# tobi_arduino_version.net
KiCad netlist of a schematic drawn in EAGLE
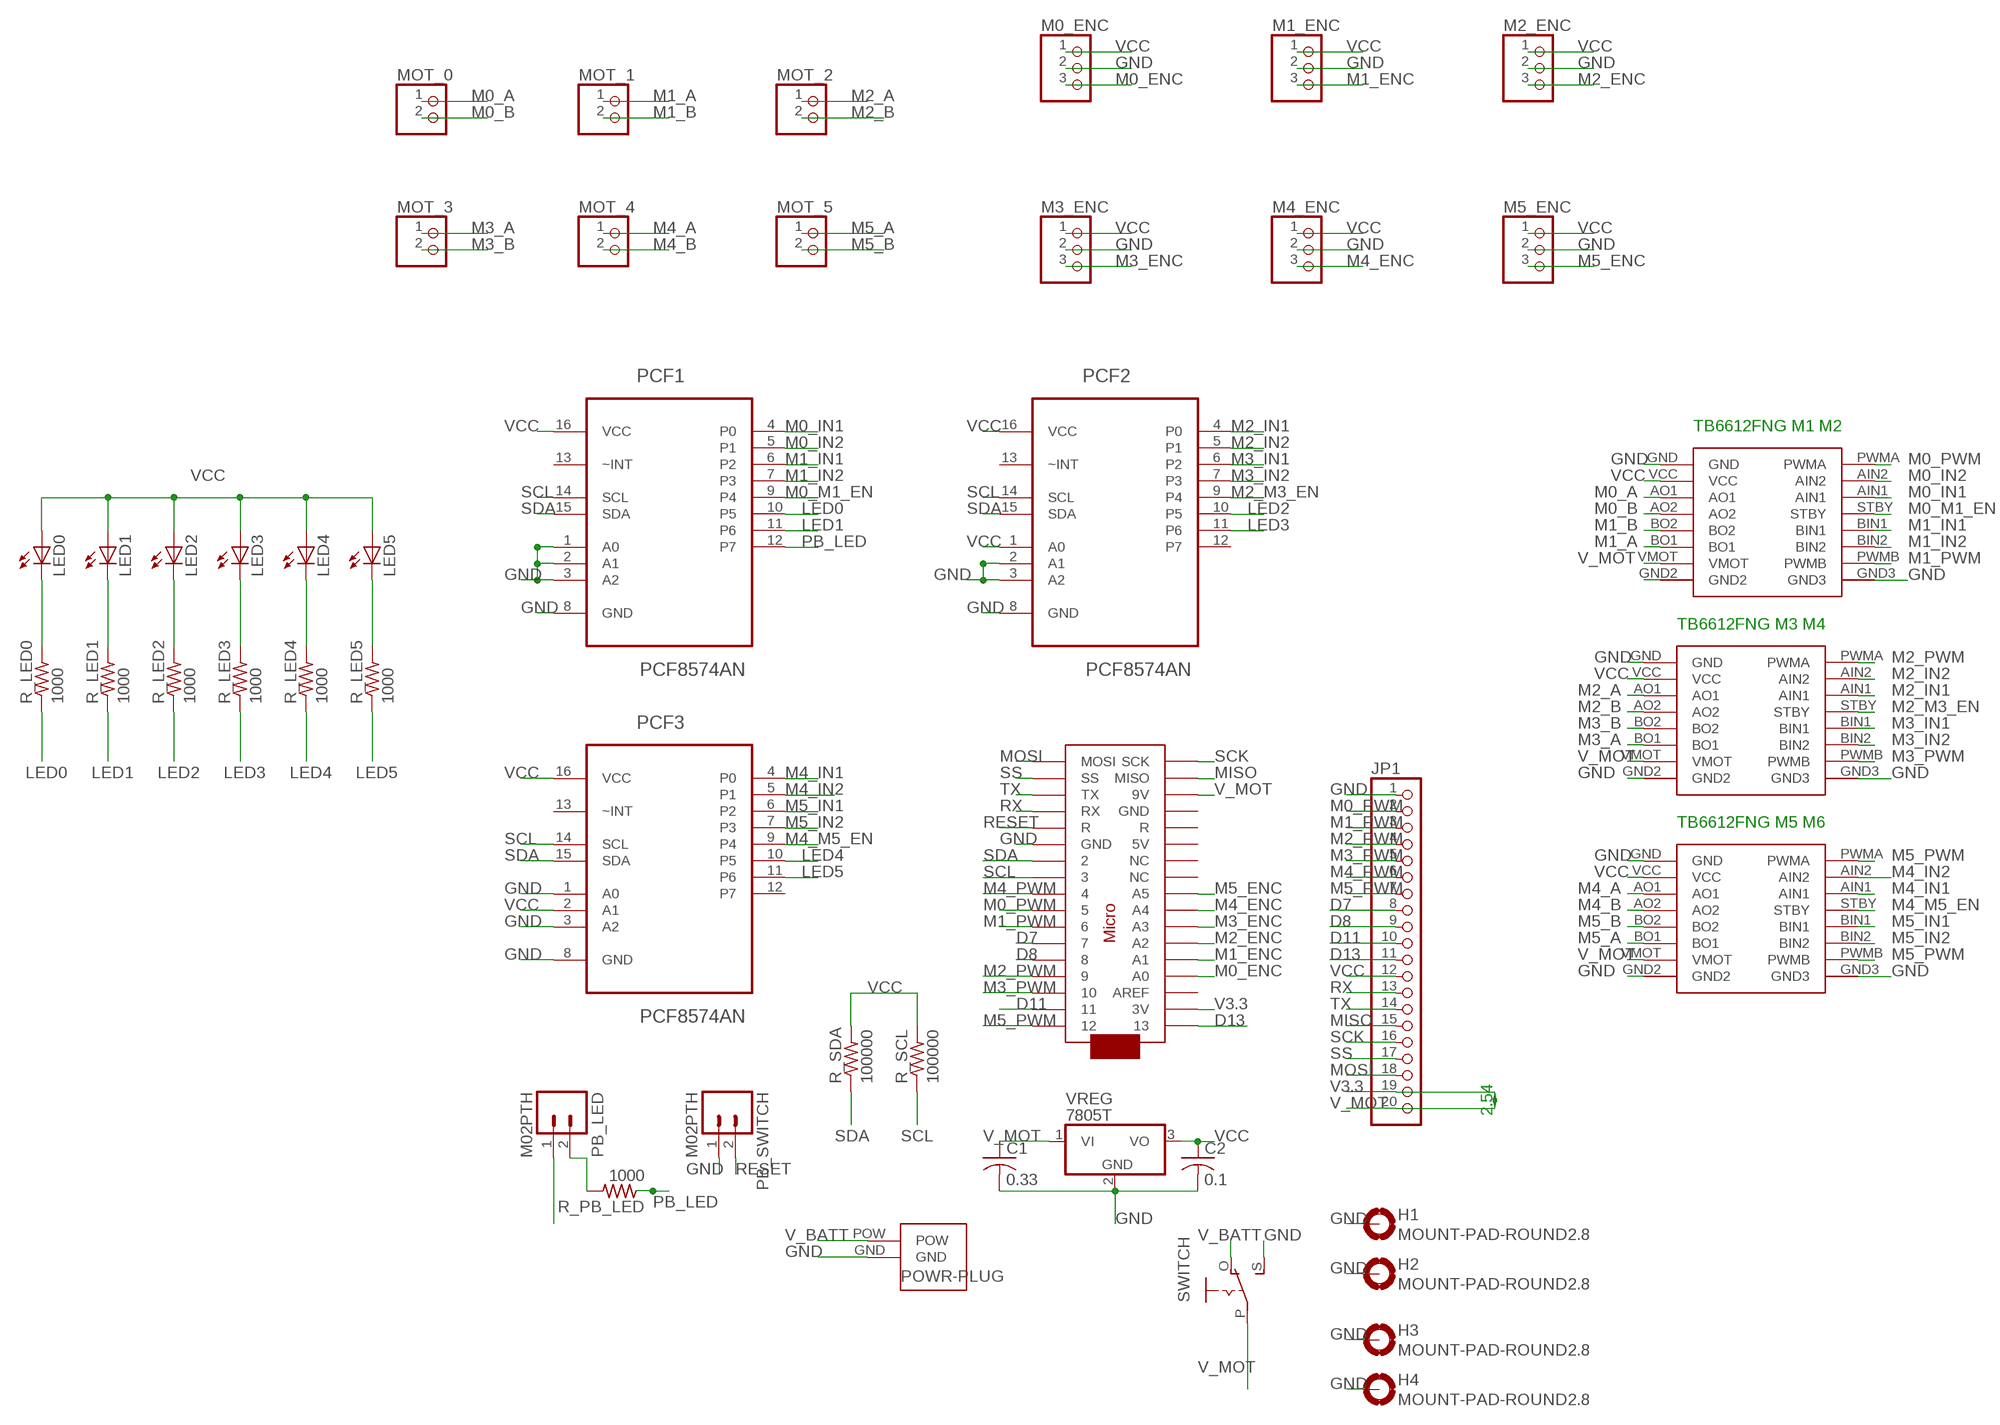
[diagram p0: schematic, sheet 1]

(export (version "E")
  (design (tool "Eeschema 10.0.6"))
  (components
    (comp (ref "ARDUINOMICRO")
      (value "ARDUINOMICRO")
      (footprint "eagle-import:ARDUINOMICRO")
      (libsource (lib "eagle-import") (part "ARDUINOMICRO"))
    )
    (comp (ref "C1")
      (value "0.33")
      (footprint "eagle-import:C025-025X050")
      (libsource (lib "eagle-import") (part "C-US025-025X050"))
    )
    (comp (ref "C2")
      (value "0.1")
      (footprint "eagle-import:C025-025X050")
      (libsource (lib "eagle-import") (part "C-US025-025X050"))
    )
    (comp (ref "DRIVER1")
      (value "POLOLU_MOTOR_DRV8835THROUGHHOLE")
      (footprint "eagle-import:POLOLU_MOTOR_DRV_DRV8835")
      (libsource (lib "eagle-import") (part "POLOLU_MOTOR_DRV8835THROUGHHOLE"))
    )
    (comp (ref "DRIVER2")
      (value "POLOLU_MOTOR_DRV8835THROUGHHOLE")
      (footprint "eagle-import:POLOLU_MOTOR_DRV_DRV8835")
      (libsource (lib "eagle-import") (part "POLOLU_MOTOR_DRV8835THROUGHHOLE"))
    )
    (comp (ref "DRIVER3")
      (value "POLOLU_MOTOR_DRV8835THROUGHHOLE")
      (footprint "eagle-import:POLOLU_MOTOR_DRV_DRV8835")
      (libsource (lib "eagle-import") (part "POLOLU_MOTOR_DRV8835THROUGHHOLE"))
    )
    (comp (ref "H1")
      (value "MOUNT-PAD-ROUND2.8")
      (footprint "eagle-import:2,8-PAD")
      (libsource (lib "eagle-import") (part "MOUNT-PAD-ROUND2.8"))
    )
    (comp (ref "H2")
      (value "MOUNT-PAD-ROUND2.8")
      (footprint "eagle-import:2,8-PAD")
      (libsource (lib "eagle-import") (part "MOUNT-PAD-ROUND2.8"))
    )
    (comp (ref "H3")
      (value "MOUNT-PAD-ROUND2.8")
      (footprint "eagle-import:2,8-PAD")
      (libsource (lib "eagle-import") (part "MOUNT-PAD-ROUND2.8"))
    )
    (comp (ref "H4")
      (value "MOUNT-PAD-ROUND2.8")
      (footprint "eagle-import:2,8-PAD")
      (libsource (lib "eagle-import") (part "MOUNT-PAD-ROUND2.8"))
    )
    (comp (ref "JP1")
      (value "PINHD-1X20")
      (footprint "eagle-import:1X20")
      (libsource (lib "eagle-import") (part "PINHD-1X20"))
    )
    (comp (ref "LED0")
      (value "LED3MM")
      (footprint "eagle-import:LED3MM")
      (libsource (lib "eagle-import") (part "LED3MM"))
    )
    (comp (ref "LED1")
      (value "LED3MM")
      (footprint "eagle-import:LED3MM")
      (libsource (lib "eagle-import") (part "LED3MM"))
    )
    (comp (ref "LED2")
      (value "LED3MM")
      (footprint "eagle-import:LED3MM")
      (libsource (lib "eagle-import") (part "LED3MM"))
    )
    (comp (ref "LED3")
      (value "LED3MM")
      (footprint "eagle-import:LED3MM")
      (libsource (lib "eagle-import") (part "LED3MM"))
    )
    (comp (ref "LED4")
      (value "LED3MM")
      (footprint "eagle-import:LED3MM")
      (libsource (lib "eagle-import") (part "LED3MM"))
    )
    (comp (ref "LED5")
      (value "LED3MM")
      (footprint "eagle-import:LED3MM")
      (libsource (lib "eagle-import") (part "LED3MM"))
    )
    (comp (ref "M0_ENC")
      (value "PINHD-1X3")
      (footprint "eagle-import:1X03")
      (libsource (lib "eagle-import") (part "PINHD-1X3"))
    )
    (comp (ref "M1_ENC")
      (value "PINHD-1X3")
      (footprint "eagle-import:1X03")
      (libsource (lib "eagle-import") (part "PINHD-1X3"))
    )
    (comp (ref "M2_ENC")
      (value "PINHD-1X3")
      (footprint "eagle-import:1X03")
      (libsource (lib "eagle-import") (part "PINHD-1X3"))
    )
    (comp (ref "M3_ENC")
      (value "PINHD-1X3")
      (footprint "eagle-import:1X03")
      (libsource (lib "eagle-import") (part "PINHD-1X3"))
    )
    (comp (ref "M4_ENC")
      (value "PINHD-1X3")
      (footprint "eagle-import:1X03")
      (libsource (lib "eagle-import") (part "PINHD-1X3"))
    )
    (comp (ref "M5_ENC")
      (value "PINHD-1X3")
      (footprint "eagle-import:1X03")
      (libsource (lib "eagle-import") (part "PINHD-1X3"))
    )
    (comp (ref "MOT_0")
      (value "PINHD-1X2")
      (footprint "eagle-import:1X02")
      (libsource (lib "eagle-import") (part "PINHD-1X2"))
    )
    (comp (ref "MOT_1")
      (value "PINHD-1X2")
      (footprint "eagle-import:1X02")
      (libsource (lib "eagle-import") (part "PINHD-1X2"))
    )
    (comp (ref "MOT_2")
      (value "PINHD-1X2")
      (footprint "eagle-import:1X02")
      (libsource (lib "eagle-import") (part "PINHD-1X2"))
    )
    (comp (ref "MOT_3")
      (value "PINHD-1X2")
      (footprint "eagle-import:1X02")
      (libsource (lib "eagle-import") (part "PINHD-1X2"))
    )
    (comp (ref "MOT_4")
      (value "PINHD-1X2")
      (footprint "eagle-import:1X02")
      (libsource (lib "eagle-import") (part "PINHD-1X2"))
    )
    (comp (ref "MOT_5")
      (value "PINHD-1X2")
      (footprint "eagle-import:1X02")
      (libsource (lib "eagle-import") (part "PINHD-1X2"))
    )
    (comp (ref "PB_LED")
      (value "M02PTH")
      (footprint "eagle-import:1X02")
      (libsource (lib "eagle-import") (part "M02PTH"))
    )
    (comp (ref "PB_SWITCH")
      (value "M02PTH")
      (footprint "eagle-import:1X02")
      (libsource (lib "eagle-import") (part "M02PTH"))
    )
    (comp (ref "PCF1")
      (value "PCF8574AN")
      (footprint "eagle-import:DIP254P762X508-16")
      (libsource (lib "eagle-import") (part "PCF8574AN"))
    )
    (comp (ref "PCF2")
      (value "PCF8574AN")
      (footprint "eagle-import:DIP254P762X508-16")
      (libsource (lib "eagle-import") (part "PCF8574AN"))
    )
    (comp (ref "PCF3")
      (value "PCF8574AN")
      (footprint "eagle-import:DIP254P762X508-16")
      (libsource (lib "eagle-import") (part "PCF8574AN"))
    )
    (comp (ref "POWR-PLUG")
      (value "MINI_DEANSSMD")
      (footprint "eagle-import:MINI_DEANS")
      (libsource (lib "eagle-import") (part "MINI_DEANSSMD"))
    )
    (comp (ref "R_LED0")
      (value "1000")
      (footprint "eagle-import:0204V")
      (libsource (lib "eagle-import") (part "R-US_0204/2V"))
    )
    (comp (ref "R_LED1")
      (value "1000")
      (footprint "eagle-import:0204V")
      (libsource (lib "eagle-import") (part "R-US_0204/2V"))
    )
    (comp (ref "R_LED2")
      (value "1000")
      (footprint "eagle-import:0204V")
      (libsource (lib "eagle-import") (part "R-US_0204/2V"))
    )
    (comp (ref "R_LED3")
      (value "1000")
      (footprint "eagle-import:0204V")
      (libsource (lib "eagle-import") (part "R-US_0204/2V"))
    )
    (comp (ref "R_LED4")
      (value "1000")
      (footprint "eagle-import:0204V")
      (libsource (lib "eagle-import") (part "R-US_0204/2V"))
    )
    (comp (ref "R_LED5")
      (value "1000")
      (footprint "eagle-import:0204V")
      (libsource (lib "eagle-import") (part "R-US_0204/2V"))
    )
    (comp (ref "R_PB_LED")
      (value "1000")
      (footprint "eagle-import:0204V")
      (libsource (lib "eagle-import") (part "R-US_0204/2V"))
    )
    (comp (ref "R_SCL")
      (value "100000")
      (footprint "eagle-import:0204V")
      (libsource (lib "eagle-import") (part "R-US_0204/2V"))
    )
    (comp (ref "R_SDA")
      (value "100000")
      (footprint "eagle-import:0204V")
      (libsource (lib "eagle-import") (part "R-US_0204/2V"))
    )
    (comp (ref "SWITCH")
      (value "EG1218S")
      (footprint "eagle-import:EG1218")
      (libsource (lib "eagle-import") (part "EG1218S"))
    )
    (comp (ref "VREG")
      (value "7805T")
      (footprint "eagle-import:TO220H")
      (libsource (lib "eagle-import") (part "78T05"))
    )
  )
  (nets
    (net (code "1") (name "/D7") (class "Default")
      (node (ref "ARDUINOMICRO") (pin "P$6") (pinfunction "7_P$6") (pintype "bidirectional"))
      (node (ref "JP1") (pin "8") (pinfunction "8_8") (pintype "passive"))
    )
    (net (code "2") (name "/D8") (class "Default")
      (node (ref "ARDUINOMICRO") (pin "P$5") (pinfunction "8_P$5") (pintype "bidirectional"))
      (node (ref "JP1") (pin "9") (pinfunction "9_9") (pintype "passive"))
    )
    (net (code "3") (name "/D11") (class "Default")
      (node (ref "ARDUINOMICRO") (pin "P$2") (pinfunction "11_P$2") (pintype "bidirectional"))
      (node (ref "JP1") (pin "10") (pinfunction "10_10") (pintype "passive"))
    )
    (net (code "4") (name "/D13") (class "Default")
      (node (ref "ARDUINOMICRO") (pin "P$34") (pinfunction "13_P$34") (pintype "bidirectional"))
      (node (ref "JP1") (pin "11") (pinfunction "11_11") (pintype "passive"))
    )
    (net (code "5") (name "/GND") (class "Default")
      (node (ref "ARDUINOMICRO") (pin "P$21") (pinfunction "GND_P$21") (pintype "bidirectional"))
      (node (ref "C1") (pin "2") (pinfunction "2_2") (pintype "passive"))
      (node (ref "C2") (pin "2") (pinfunction "2_2") (pintype "passive"))
      (node (ref "DRIVER1") (pin "GND") (pinfunction "GND_GND") (pintype "bidirectional"))
      (node (ref "DRIVER1") (pin "GND2") (pinfunction "GND2_GND2") (pintype "bidirectional"))
      (node (ref "DRIVER1") (pin "GND3") (pinfunction "GND3_GND3") (pintype "bidirectional"))
      (node (ref "DRIVER2") (pin "GND") (pinfunction "GND_GND") (pintype "bidirectional"))
      (node (ref "DRIVER2") (pin "GND2") (pinfunction "GND2_GND2") (pintype "bidirectional"))
      (node (ref "DRIVER2") (pin "GND3") (pinfunction "GND3_GND3") (pintype "bidirectional"))
      (node (ref "DRIVER3") (pin "GND") (pinfunction "GND_GND") (pintype "bidirectional"))
      (node (ref "DRIVER3") (pin "GND2") (pinfunction "GND2_GND2") (pintype "bidirectional"))
      (node (ref "DRIVER3") (pin "GND3") (pinfunction "GND3_GND3") (pintype "bidirectional"))
      (node (ref "H1") (pin "B2,8") (pinfunction "MOUNT_B2,8") (pintype "passive"))
      (node (ref "H2") (pin "B2,8") (pinfunction "MOUNT_B2,8") (pintype "passive"))
      (node (ref "H3") (pin "B2,8") (pinfunction "MOUNT_B2,8") (pintype "passive"))
      (node (ref "H4") (pin "B2,8") (pinfunction "MOUNT_B2,8") (pintype "passive"))
      (node (ref "JP1") (pin "1") (pinfunction "1_1") (pintype "passive"))
      (node (ref "M0_ENC") (pin "2") (pinfunction "2_2") (pintype "passive"))
      (node (ref "M1_ENC") (pin "2") (pinfunction "2_2") (pintype "passive"))
      (node (ref "M2_ENC") (pin "2") (pinfunction "2_2") (pintype "passive"))
      (node (ref "M3_ENC") (pin "2") (pinfunction "2_2") (pintype "passive"))
      (node (ref "M4_ENC") (pin "2") (pinfunction "2_2") (pintype "passive"))
      (node (ref "M5_ENC") (pin "2") (pinfunction "2_2") (pintype "passive"))
      (node (ref "PB_SWITCH") (pin "1") (pinfunction "1_1") (pintype "passive"))
      (node (ref "PCF1") (pin "1") (pinfunction "A0_1") (pintype "input"))
      (node (ref "PCF1") (pin "2") (pinfunction "A1_2") (pintype "input"))
      (node (ref "PCF1") (pin "3") (pinfunction "A2_3") (pintype "input"))
      (node (ref "PCF1") (pin "8") (pinfunction "GND_8") (pintype "passive"))
      (node (ref "PCF2") (pin "2") (pinfunction "A1_2") (pintype "input"))
      (node (ref "PCF2") (pin "3") (pinfunction "A2_3") (pintype "input"))
      (node (ref "PCF2") (pin "8") (pinfunction "GND_8") (pintype "passive"))
      (node (ref "PCF3") (pin "1") (pinfunction "A0_1") (pintype "input"))
      (node (ref "PCF3") (pin "3") (pinfunction "A2_3") (pintype "input"))
      (node (ref "PCF3") (pin "8") (pinfunction "GND_8") (pintype "passive"))
      (node (ref "POWR-PLUG") (pin "GND") (pinfunction "GND_GND") (pintype "bidirectional"))
      (node (ref "SWITCH") (pin "S") (pinfunction "S_S") (pintype "passive"))
      (node (ref "VREG") (pin "2") (pinfunction "GND_2") (pintype "passive"))
    )
    (net (code "6") (name "/LED0") (class "Default")
      (node (ref "LED0") (pin "K") (pinfunction "C_K") (pintype "passive"))
      (node (ref "PCF1") (pin "10") (pinfunction "P5_10") (pintype "bidirectional"))
      (node (ref "R_LED0") (pin "1") (pinfunction "1_1") (pintype "passive"))
      (node (ref "R_LED0") (pin "2") (pinfunction "2_2") (pintype "passive"))
    )
    (net (code "7") (name "/LED1") (class "Default")
      (node (ref "LED1") (pin "K") (pinfunction "C_K") (pintype "passive"))
      (node (ref "PCF1") (pin "11") (pinfunction "P6_11") (pintype "bidirectional"))
      (node (ref "R_LED1") (pin "1") (pinfunction "1_1") (pintype "passive"))
      (node (ref "R_LED1") (pin "2") (pinfunction "2_2") (pintype "passive"))
    )
    (net (code "8") (name "/LED2") (class "Default")
      (node (ref "LED2") (pin "K") (pinfunction "C_K") (pintype "passive"))
      (node (ref "PCF2") (pin "10") (pinfunction "P5_10") (pintype "bidirectional"))
      (node (ref "R_LED2") (pin "1") (pinfunction "1_1") (pintype "passive"))
      (node (ref "R_LED2") (pin "2") (pinfunction "2_2") (pintype "passive"))
    )
    (net (code "9") (name "/LED3") (class "Default")
      (node (ref "LED3") (pin "K") (pinfunction "C_K") (pintype "passive"))
      (node (ref "PCF2") (pin "11") (pinfunction "P6_11") (pintype "bidirectional"))
      (node (ref "R_LED3") (pin "1") (pinfunction "1_1") (pintype "passive"))
      (node (ref "R_LED3") (pin "2") (pinfunction "2_2") (pintype "passive"))
    )
    (net (code "10") (name "/LED4") (class "Default")
      (node (ref "LED4") (pin "K") (pinfunction "C_K") (pintype "passive"))
      (node (ref "PCF3") (pin "10") (pinfunction "P5_10") (pintype "bidirectional"))
      (node (ref "R_LED4") (pin "1") (pinfunction "1_1") (pintype "passive"))
      (node (ref "R_LED4") (pin "2") (pinfunction "2_2") (pintype "passive"))
    )
    (net (code "11") (name "/LED5") (class "Default")
      (node (ref "LED5") (pin "K") (pinfunction "C_K") (pintype "passive"))
      (node (ref "PCF3") (pin "11") (pinfunction "P6_11") (pintype "bidirectional"))
      (node (ref "R_LED5") (pin "1") (pinfunction "1_1") (pintype "passive"))
      (node (ref "R_LED5") (pin "2") (pinfunction "2_2") (pintype "passive"))
    )
    (net (code "12") (name "/M0_A") (class "Default")
      (node (ref "DRIVER1") (pin "AO1") (pinfunction "AO1_AO1") (pintype "bidirectional"))
      (node (ref "MOT_0") (pin "1") (pinfunction "1_1") (pintype "passive"))
    )
    (net (code "13") (name "/M0_B") (class "Default")
      (node (ref "DRIVER1") (pin "AO2") (pinfunction "AO2_AO2") (pintype "bidirectional"))
      (node (ref "MOT_0") (pin "2") (pinfunction "2_2") (pintype "passive"))
    )
    (net (code "14") (name "/M0_ENC") (class "Default")
      (node (ref "ARDUINOMICRO") (pin "P$31") (pinfunction "A0_P$31") (pintype "bidirectional"))
      (node (ref "M0_ENC") (pin "3") (pinfunction "3_3") (pintype "passive"))
    )
    (net (code "15") (name "/M0_IN1") (class "Default")
      (node (ref "DRIVER1") (pin "AIN1") (pinfunction "AIN1_AIN1") (pintype "bidirectional"))
      (node (ref "PCF1") (pin "4") (pinfunction "P0_4") (pintype "bidirectional"))
    )
    (net (code "16") (name "/M0_IN2") (class "Default")
      (node (ref "DRIVER1") (pin "AIN2") (pinfunction "AIN2_AIN2") (pintype "bidirectional"))
      (node (ref "PCF1") (pin "5") (pinfunction "P1_5") (pintype "bidirectional"))
    )
    (net (code "17") (name "/M0_M1_EN") (class "Default")
      (node (ref "DRIVER1") (pin "STBY") (pinfunction "STBY_STBY") (pintype "bidirectional"))
      (node (ref "PCF1") (pin "9") (pinfunction "P4_9") (pintype "bidirectional"))
    )
    (net (code "18") (name "/M0_PWM") (class "Default")
      (node (ref "ARDUINOMICRO") (pin "P$8") (pinfunction "5_P$8") (pintype "bidirectional"))
      (node (ref "DRIVER1") (pin "PWMA") (pinfunction "PWMA_PWMA") (pintype "bidirectional"))
      (node (ref "JP1") (pin "2") (pinfunction "2_2") (pintype "passive"))
    )
    (net (code "19") (name "/M1_A") (class "Default")
      (node (ref "DRIVER1") (pin "BO1") (pinfunction "BO1_BO1") (pintype "bidirectional"))
      (node (ref "MOT_1") (pin "1") (pinfunction "1_1") (pintype "passive"))
    )
    (net (code "20") (name "/M1_B") (class "Default")
      (node (ref "DRIVER1") (pin "BO2") (pinfunction "BO2_BO2") (pintype "bidirectional"))
      (node (ref "MOT_1") (pin "2") (pinfunction "2_2") (pintype "passive"))
    )
    (net (code "21") (name "/M1_ENC") (class "Default")
      (node (ref "ARDUINOMICRO") (pin "P$30") (pinfunction "A1_P$30") (pintype "bidirectional"))
      (node (ref "M1_ENC") (pin "3") (pinfunction "3_3") (pintype "passive"))
    )
    (net (code "22") (name "/M1_IN1") (class "Default")
      (node (ref "DRIVER1") (pin "BIN1") (pinfunction "BIN1_BIN1") (pintype "bidirectional"))
      (node (ref "PCF1") (pin "6") (pinfunction "P2_6") (pintype "bidirectional"))
    )
    (net (code "23") (name "/M1_IN2") (class "Default")
      (node (ref "DRIVER1") (pin "BIN2") (pinfunction "BIN2_BIN2") (pintype "bidirectional"))
      (node (ref "PCF1") (pin "7") (pinfunction "P3_7") (pintype "bidirectional"))
    )
    (net (code "24") (name "/M1_PWM") (class "Default")
      (node (ref "ARDUINOMICRO") (pin "P$7") (pinfunction "6_P$7") (pintype "bidirectional"))
      (node (ref "DRIVER1") (pin "PWMB") (pinfunction "PWMB_PWMB") (pintype "bidirectional"))
      (node (ref "JP1") (pin "3") (pinfunction "3_3") (pintype "passive"))
    )
    (net (code "25") (name "/M2_A") (class "Default")
      (node (ref "DRIVER2") (pin "AO1") (pinfunction "AO1_AO1") (pintype "bidirectional"))
      (node (ref "MOT_2") (pin "1") (pinfunction "1_1") (pintype "passive"))
    )
    (net (code "26") (name "/M2_B") (class "Default")
      (node (ref "DRIVER2") (pin "AO2") (pinfunction "AO2_AO2") (pintype "bidirectional"))
      (node (ref "MOT_2") (pin "2") (pinfunction "2_2") (pintype "passive"))
    )
    (net (code "27") (name "/M2_ENC") (class "Default")
      (node (ref "ARDUINOMICRO") (pin "P$29") (pinfunction "A2_P$29") (pintype "bidirectional"))
      (node (ref "M2_ENC") (pin "3") (pinfunction "3_3") (pintype "passive"))
    )
    (net (code "28") (name "/M2_IN1") (class "Default")
      (node (ref "DRIVER2") (pin "AIN1") (pinfunction "AIN1_AIN1") (pintype "bidirectional"))
      (node (ref "PCF2") (pin "4") (pinfunction "P0_4") (pintype "bidirectional"))
    )
    (net (code "29") (name "/M2_IN2") (class "Default")
      (node (ref "DRIVER2") (pin "AIN2") (pinfunction "AIN2_AIN2") (pintype "bidirectional"))
      (node (ref "PCF2") (pin "5") (pinfunction "P1_5") (pintype "bidirectional"))
    )
    (net (code "30") (name "/M2_M3_EN") (class "Default")
      (node (ref "DRIVER2") (pin "STBY") (pinfunction "STBY_STBY") (pintype "bidirectional"))
      (node (ref "PCF2") (pin "9") (pinfunction "P4_9") (pintype "bidirectional"))
    )
    (net (code "31") (name "/M2_PWM") (class "Default")
      (node (ref "ARDUINOMICRO") (pin "P$4") (pinfunction "9_P$4") (pintype "bidirectional"))
      (node (ref "DRIVER2") (pin "PWMA") (pinfunction "PWMA_PWMA") (pintype "bidirectional"))
      (node (ref "JP1") (pin "4") (pinfunction "4_4") (pintype "passive"))
    )
    (net (code "32") (name "/M3_A") (class "Default")
      (node (ref "DRIVER2") (pin "BO1") (pinfunction "BO1_BO1") (pintype "bidirectional"))
      (node (ref "MOT_3") (pin "1") (pinfunction "1_1") (pintype "passive"))
    )
    (net (code "33") (name "/M3_B") (class "Default")
      (node (ref "DRIVER2") (pin "BO2") (pinfunction "BO2_BO2") (pintype "bidirectional"))
      (node (ref "MOT_3") (pin "2") (pinfunction "2_2") (pintype "passive"))
    )
    (net (code "34") (name "/M3_ENC") (class "Default")
      (node (ref "ARDUINOMICRO") (pin "P$28") (pinfunction "A3_P$28") (pintype "bidirectional"))
      (node (ref "M3_ENC") (pin "3") (pinfunction "3_3") (pintype "passive"))
    )
    (net (code "35") (name "/M3_IN1") (class "Default")
      (node (ref "DRIVER2") (pin "BIN1") (pinfunction "BIN1_BIN1") (pintype "bidirectional"))
      (node (ref "PCF2") (pin "6") (pinfunction "P2_6") (pintype "bidirectional"))
    )
    (net (code "36") (name "/M3_IN2") (class "Default")
      (node (ref "DRIVER2") (pin "BIN2") (pinfunction "BIN2_BIN2") (pintype "bidirectional"))
      (node (ref "PCF2") (pin "7") (pinfunction "P3_7") (pintype "bidirectional"))
    )
    (net (code "37") (name "/M3_PWM") (class "Default")
      (node (ref "ARDUINOMICRO") (pin "P$3") (pinfunction "10_P$3") (pintype "bidirectional"))
      (node (ref "DRIVER2") (pin "PWMB") (pinfunction "PWMB_PWMB") (pintype "bidirectional"))
      (node (ref "JP1") (pin "5") (pinfunction "5_5") (pintype "passive"))
    )
    (net (code "38") (name "/M4_A") (class "Default")
      (node (ref "DRIVER3") (pin "AO1") (pinfunction "AO1_AO1") (pintype "bidirectional"))
      (node (ref "MOT_4") (pin "1") (pinfunction "1_1") (pintype "passive"))
    )
    (net (code "39") (name "/M4_B") (class "Default")
      (node (ref "DRIVER3") (pin "AO2") (pinfunction "AO2_AO2") (pintype "bidirectional"))
      (node (ref "MOT_4") (pin "2") (pinfunction "2_2") (pintype "passive"))
    )
    (net (code "40") (name "/M4_ENC") (class "Default")
      (node (ref "ARDUINOMICRO") (pin "P$27") (pinfunction "A4_P$27") (pintype "bidirectional"))
      (node (ref "M4_ENC") (pin "3") (pinfunction "3_3") (pintype "passive"))
    )
    (net (code "41") (name "/M4_IN1") (class "Default")
      (node (ref "DRIVER3") (pin "AIN1") (pinfunction "AIN1_AIN1") (pintype "bidirectional"))
      (node (ref "PCF3") (pin "4") (pinfunction "P0_4") (pintype "bidirectional"))
    )
    (net (code "42") (name "/M4_IN2") (class "Default")
      (node (ref "DRIVER3") (pin "AIN2") (pinfunction "AIN2_AIN2") (pintype "bidirectional"))
      (node (ref "PCF3") (pin "5") (pinfunction "P1_5") (pintype "bidirectional"))
    )
    (net (code "43") (name "/M4_M5_EN") (class "Default")
      (node (ref "DRIVER3") (pin "STBY") (pinfunction "STBY_STBY") (pintype "bidirectional"))
      (node (ref "PCF3") (pin "9") (pinfunction "P4_9") (pintype "bidirectional"))
    )
    (net (code "44") (name "/M4_PWM") (class "Default")
      (node (ref "ARDUINOMICRO") (pin "P$9") (pinfunction "4_P$9") (pintype "bidirectional"))
      (node (ref "JP1") (pin "6") (pinfunction "6_6") (pintype "passive"))
    )
    (net (code "45") (name "/M5_A") (class "Default")
      (node (ref "DRIVER3") (pin "BO1") (pinfunction "BO1_BO1") (pintype "bidirectional"))
      (node (ref "MOT_5") (pin "1") (pinfunction "1_1") (pintype "passive"))
    )
    (net (code "46") (name "/M5_B") (class "Default")
      (node (ref "DRIVER3") (pin "BO2") (pinfunction "BO2_BO2") (pintype "bidirectional"))
      (node (ref "MOT_5") (pin "2") (pinfunction "2_2") (pintype "passive"))
    )
    (net (code "47") (name "/M5_ENC") (class "Default")
      (node (ref "ARDUINOMICRO") (pin "P$26") (pinfunction "A5_P$26") (pintype "bidirectional"))
      (node (ref "M5_ENC") (pin "3") (pinfunction "3_3") (pintype "passive"))
    )
    (net (code "48") (name "/M5_IN1") (class "Default")
      (node (ref "DRIVER3") (pin "BIN1") (pinfunction "BIN1_BIN1") (pintype "bidirectional"))
      (node (ref "PCF3") (pin "6") (pinfunction "P2_6") (pintype "bidirectional"))
    )
    (net (code "49") (name "/M5_IN2") (class "Default")
      (node (ref "DRIVER3") (pin "BIN2") (pinfunction "BIN2_BIN2") (pintype "bidirectional"))
      (node (ref "PCF3") (pin "7") (pinfunction "P3_7") (pintype "bidirectional"))
    )
    (net (code "50") (name "/M5_PWM") (class "Default")
      (node (ref "ARDUINOMICRO") (pin "P$1") (pinfunction "12_P$1") (pintype "bidirectional"))
      (node (ref "DRIVER3") (pin "PWMA") (pinfunction "PWMA_PWMA") (pintype "bidirectional"))
      (node (ref "DRIVER3") (pin "PWMB") (pinfunction "PWMB_PWMB") (pintype "bidirectional"))
      (node (ref "JP1") (pin "7") (pinfunction "7_7") (pintype "passive"))
    )
    (net (code "51") (name "/MISO") (class "Default")
      (node (ref "ARDUINOMICRO") (pin "P$19") (pinfunction "MISO_P$19") (pintype "bidirectional"))
      (node (ref "JP1") (pin "15") (pinfunction "15_15") (pintype "passive"))
    )
    (net (code "52") (name "/MOSI") (class "Default")
      (node (ref "ARDUINOMICRO") (pin "P$17") (pinfunction "MOSI_P$17") (pintype "bidirectional"))
      (node (ref "JP1") (pin "18") (pinfunction "18_18") (pintype "passive"))
    )
    (net (code "53") (name "/PB_LED") (class "Default")
      (node (ref "PCF1") (pin "12") (pinfunction "P7_12") (pintype "bidirectional"))
      (node (ref "R_PB_LED") (pin "1") (pinfunction "1_1") (pintype "passive"))
    )
    (net (code "54") (name "/RESET") (class "Default")
      (node (ref "ARDUINOMICRO") (pin "P$22") (pinfunction "R_P$22") (pintype "bidirectional"))
      (node (ref "PB_SWITCH") (pin "2") (pinfunction "2_2") (pintype "passive"))
    )
    (net (code "55") (name "/RX") (class "Default")
      (node (ref "ARDUINOMICRO") (pin "P$14") (pinfunction "RX_P$14") (pintype "bidirectional"))
      (node (ref "JP1") (pin "13") (pinfunction "13_13") (pintype "passive"))
    )
    (net (code "56") (name "/SCK") (class "Default")
      (node (ref "ARDUINOMICRO") (pin "P$18") (pinfunction "SCK_P$18") (pintype "bidirectional"))
      (node (ref "JP1") (pin "16") (pinfunction "16_16") (pintype "passive"))
    )
    (net (code "57") (name "/SCL") (class "Default")
      (node (ref "ARDUINOMICRO") (pin "P$10") (pinfunction "3_P$10") (pintype "bidirectional"))
      (node (ref "PCF1") (pin "14") (pinfunction "SCL_14") (pintype "input"))
      (node (ref "PCF2") (pin "14") (pinfunction "SCL_14") (pintype "input"))
      (node (ref "PCF3") (pin "14") (pinfunction "SCL_14") (pintype "input"))
      (node (ref "R_SCL") (pin "1") (pinfunction "1_1") (pintype "passive"))
    )
    (net (code "58") (name "/SDA") (class "Default")
      (node (ref "ARDUINOMICRO") (pin "P$11") (pinfunction "2_P$11") (pintype "bidirectional"))
      (node (ref "PCF1") (pin "15") (pinfunction "SDA_15") (pintype "bidirectional"))
      (node (ref "PCF2") (pin "15") (pinfunction "SDA_15") (pintype "bidirectional"))
      (node (ref "PCF3") (pin "15") (pinfunction "SDA_15") (pintype "bidirectional"))
      (node (ref "R_SDA") (pin "1") (pinfunction "1_1") (pintype "passive"))
    )
    (net (code "59") (name "/SS") (class "Default")
      (node (ref "ARDUINOMICRO") (pin "P$16") (pinfunction "SS_P$16") (pintype "bidirectional"))
      (node (ref "JP1") (pin "17") (pinfunction "17_17") (pintype "passive"))
    )
    (net (code "60") (name "/TX") (class "Default")
      (node (ref "ARDUINOMICRO") (pin "P$15") (pinfunction "TX_P$15") (pintype "bidirectional"))
      (node (ref "JP1") (pin "14") (pinfunction "14_14") (pintype "passive"))
    )
    (net (code "61") (name "/V3.3") (class "Default")
      (node (ref "ARDUINOMICRO") (pin "P$33") (pinfunction "3V_P$33") (pintype "bidirectional"))
      (node (ref "JP1") (pin "19") (pinfunction "19_19") (pintype "passive"))
    )
    (net (code "62") (name "/VCC") (class "Default")
      (node (ref "C2") (pin "1") (pinfunction "1_1") (pintype "passive"))
      (node (ref "DRIVER1") (pin "VCC") (pinfunction "VCC_VCC") (pintype "bidirectional"))
      (node (ref "DRIVER2") (pin "VCC") (pinfunction "VCC_VCC") (pintype "bidirectional"))
      (node (ref "DRIVER3") (pin "VCC") (pinfunction "VCC_VCC") (pintype "bidirectional"))
      (node (ref "JP1") (pin "12") (pinfunction "12_12") (pintype "passive"))
      (node (ref "LED0") (pin "A") (pinfunction "A_A") (pintype "passive"))
      (node (ref "LED1") (pin "A") (pinfunction "A_A") (pintype "passive"))
      (node (ref "LED2") (pin "A") (pinfunction "A_A") (pintype "passive"))
      (node (ref "LED3") (pin "A") (pinfunction "A_A") (pintype "passive"))
      (node (ref "LED4") (pin "A") (pinfunction "A_A") (pintype "passive"))
      (node (ref "LED5") (pin "A") (pinfunction "A_A") (pintype "passive"))
      (node (ref "M0_ENC") (pin "1") (pinfunction "1_1") (pintype "passive"))
      (node (ref "M1_ENC") (pin "1") (pinfunction "1_1") (pintype "passive"))
      (node (ref "M2_ENC") (pin "1") (pinfunction "1_1") (pintype "passive"))
      (node (ref "M3_ENC") (pin "1") (pinfunction "1_1") (pintype "passive"))
      (node (ref "M4_ENC") (pin "1") (pinfunction "1_1") (pintype "passive"))
      (node (ref "M5_ENC") (pin "1") (pinfunction "1_1") (pintype "passive"))
      (node (ref "PB_LED") (pin "1") (pinfunction "1_1") (pintype "passive"))
      (node (ref "PCF1") (pin "16") (pinfunction "VCC_16") (pintype "power_in"))
      (node (ref "PCF2") (pin "1") (pinfunction "A0_1") (pintype "input"))
      (node (ref "PCF2") (pin "16") (pinfunction "VCC_16") (pintype "power_in"))
      (node (ref "PCF3") (pin "16") (pinfunction "VCC_16") (pintype "power_in"))
      (node (ref "PCF3") (pin "2") (pinfunction "A1_2") (pintype "input"))
      (node (ref "R_SCL") (pin "2") (pinfunction "2_2") (pintype "passive"))
      (node (ref "R_SDA") (pin "2") (pinfunction "2_2") (pintype "passive"))
      (node (ref "VREG") (pin "3") (pinfunction "VO_3") (pintype "passive"))
    )
    (net (code "63") (name "/V_BATT") (class "Default")
      (node (ref "POWR-PLUG") (pin "POW") (pinfunction "POW_POW") (pintype "bidirectional"))
      (node (ref "SWITCH") (pin "O") (pinfunction "O_O") (pintype "passive"))
    )
    (net (code "64") (name "/V_MOT") (class "Default")
      (node (ref "ARDUINOMICRO") (pin "P$20") (pinfunction "9V_P$20") (pintype "bidirectional"))
      (node (ref "C1") (pin "1") (pinfunction "1_1") (pintype "passive"))
      (node (ref "DRIVER1") (pin "VMOT") (pinfunction "VMOT_VMOT") (pintype "bidirectional"))
      (node (ref "DRIVER2") (pin "VMOT") (pinfunction "VMOT_VMOT") (pintype "bidirectional"))
      (node (ref "DRIVER3") (pin "VMOT") (pinfunction "VMOT_VMOT") (pintype "bidirectional"))
      (node (ref "JP1") (pin "20") (pinfunction "20_20") (pintype "passive"))
      (node (ref "SWITCH") (pin "P") (pinfunction "P_P") (pintype "passive"))
      (node (ref "VREG") (pin "1") (pinfunction "VI_1") (pintype "input"))
    )
    (net (code "65") (name "Net-(PB_LED-Pad2)") (class "Default")
      (node (ref "PB_LED") (pin "2") (pinfunction "2_2") (pintype "passive"))
      (node (ref "R_PB_LED") (pin "2") (pinfunction "2_2") (pintype "passive"))
    )
    (net (code "66") (name "unconnected-(ARDUINOMICRO-5V-PadP$23)") (class "Default")
      (node (ref "ARDUINOMICRO") (pin "P$23") (pinfunction "5V_P$23") (pintype "bidirectional"))
    )
    (net (code "67") (name "unconnected-(ARDUINOMICRO-AREF-PadP$32)") (class "Default")
      (node (ref "ARDUINOMICRO") (pin "P$32") (pinfunction "AREF_P$32") (pintype "bidirectional"))
    )
    (net (code "68") (name "unconnected-(ARDUINOMICRO-GND-PadP$12)") (class "Default")
      (node (ref "ARDUINOMICRO") (pin "P$12") (pinfunction "GND_P$12") (pintype "bidirectional"))
    )
    (net (code "69") (name "unconnected-(ARDUINOMICRO-NC-PadP$24)") (class "Default")
      (node (ref "ARDUINOMICRO") (pin "P$24") (pinfunction "NC_P$24") (pintype "bidirectional"))
    )
    (net (code "70") (name "unconnected-(ARDUINOMICRO-NC-PadP$25)") (class "Default")
      (node (ref "ARDUINOMICRO") (pin "P$25") (pinfunction "NC_P$25") (pintype "bidirectional"))
    )
    (net (code "71") (name "unconnected-(ARDUINOMICRO-R-PadP$13)") (class "Default")
      (node (ref "ARDUINOMICRO") (pin "P$13") (pinfunction "R_P$13") (pintype "bidirectional"))
    )
    (net (code "72") (name "unconnected-(PCF1-~{INT}-Pad13)") (class "Default")
      (node (ref "PCF1") (pin "13") (pinfunction "~{INT}_13") (pintype "input"))
    )
    (net (code "73") (name "unconnected-(PCF2-P7-Pad12)") (class "Default")
      (node (ref "PCF2") (pin "12") (pinfunction "P7_12") (pintype "bidirectional"))
    )
    (net (code "74") (name "unconnected-(PCF2-~{INT}-Pad13)") (class "Default")
      (node (ref "PCF2") (pin "13") (pinfunction "~{INT}_13") (pintype "input"))
    )
    (net (code "75") (name "unconnected-(PCF3-P7-Pad12)") (class "Default")
      (node (ref "PCF3") (pin "12") (pinfunction "P7_12") (pintype "bidirectional"))
    )
    (net (code "76") (name "unconnected-(PCF3-~{INT}-Pad13)") (class "Default")
      (node (ref "PCF3") (pin "13") (pinfunction "~{INT}_13") (pintype "input"))
    )
  )
)
